# design.net
KiCad netlist of a schematic drawn in Altium Designer
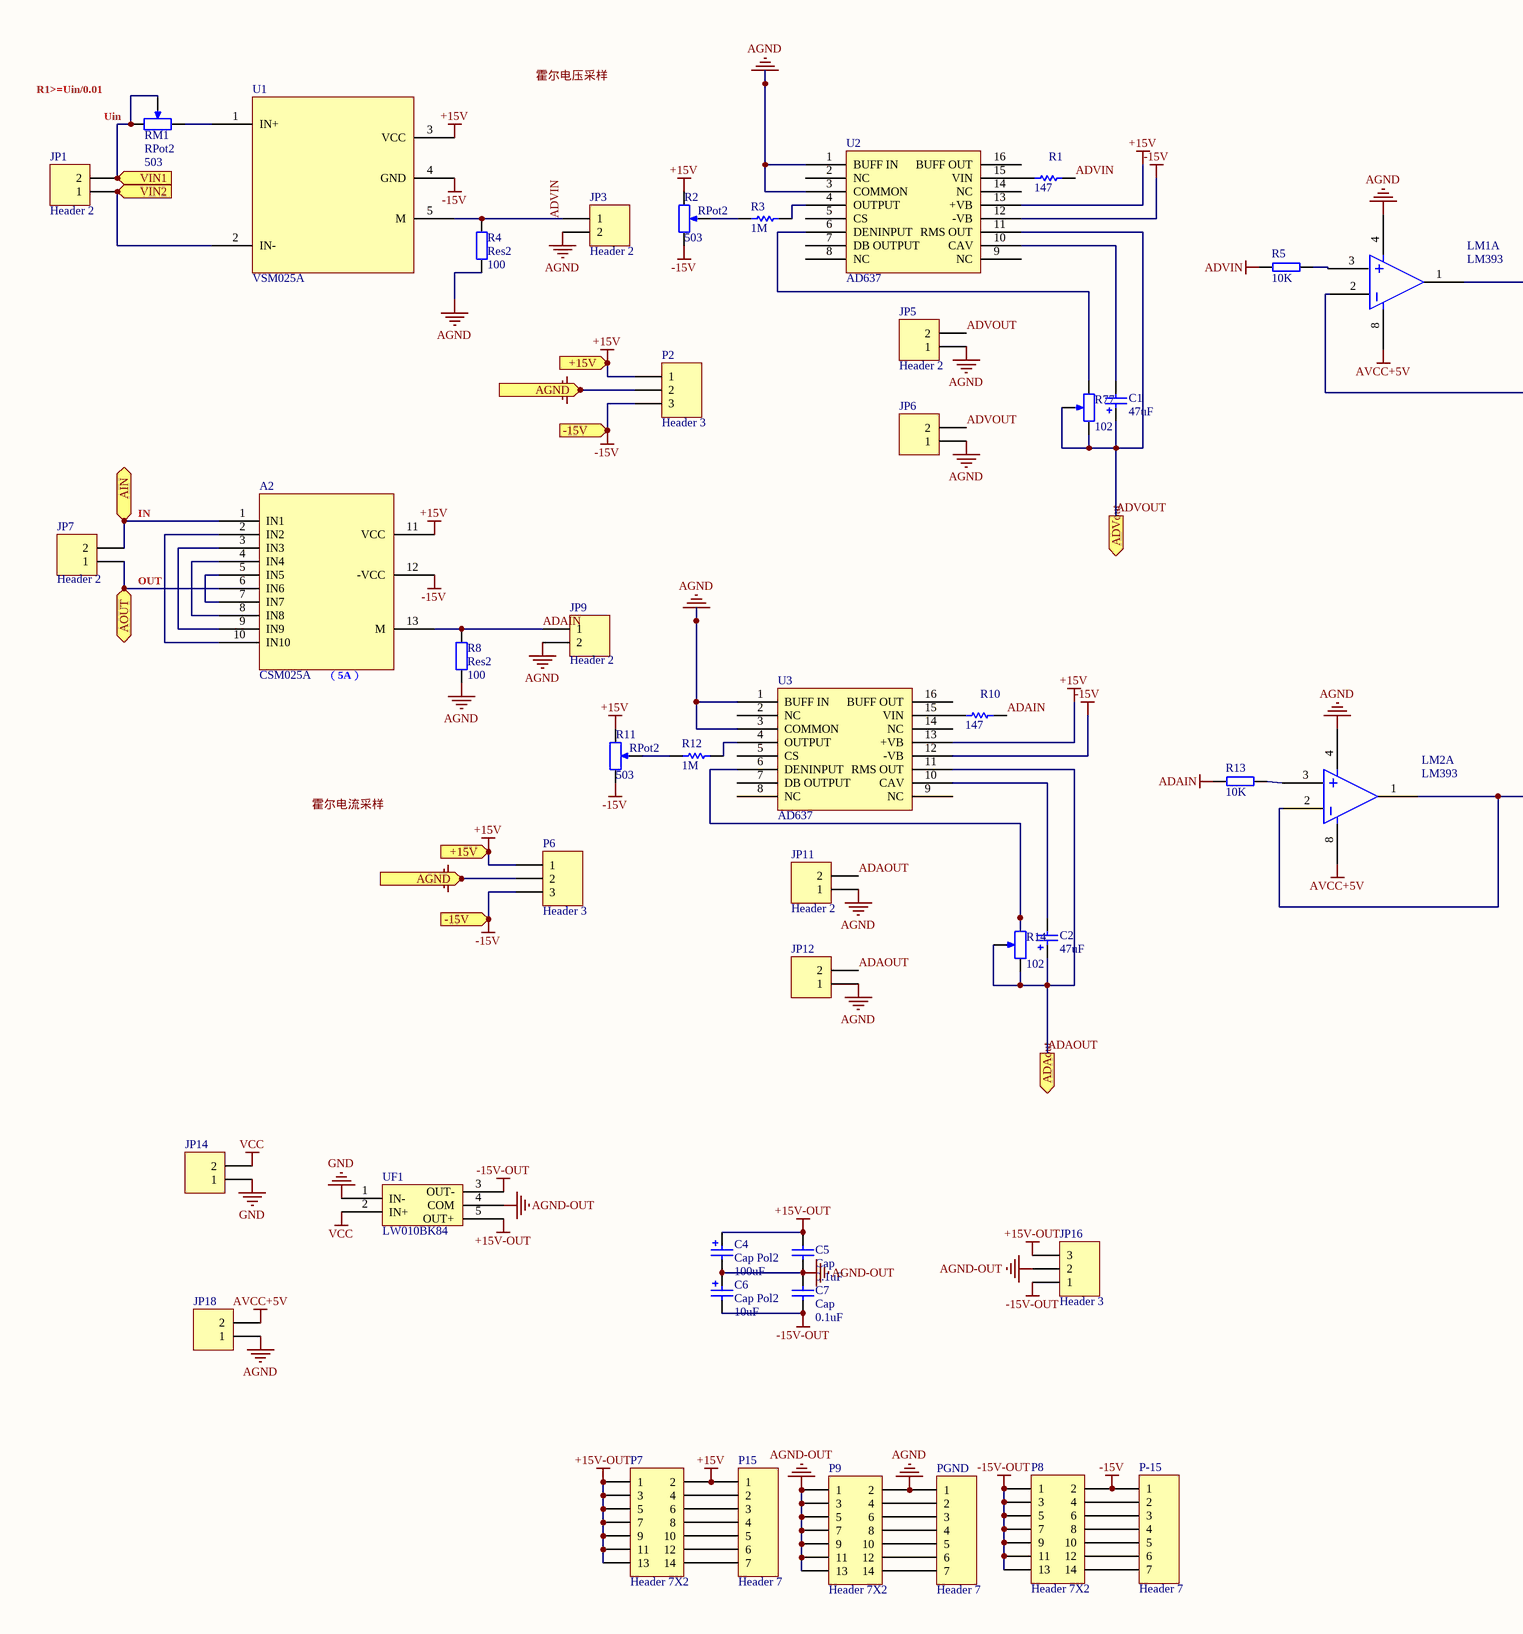
[diagram p0: 输出采样部分.SchDoc, left]
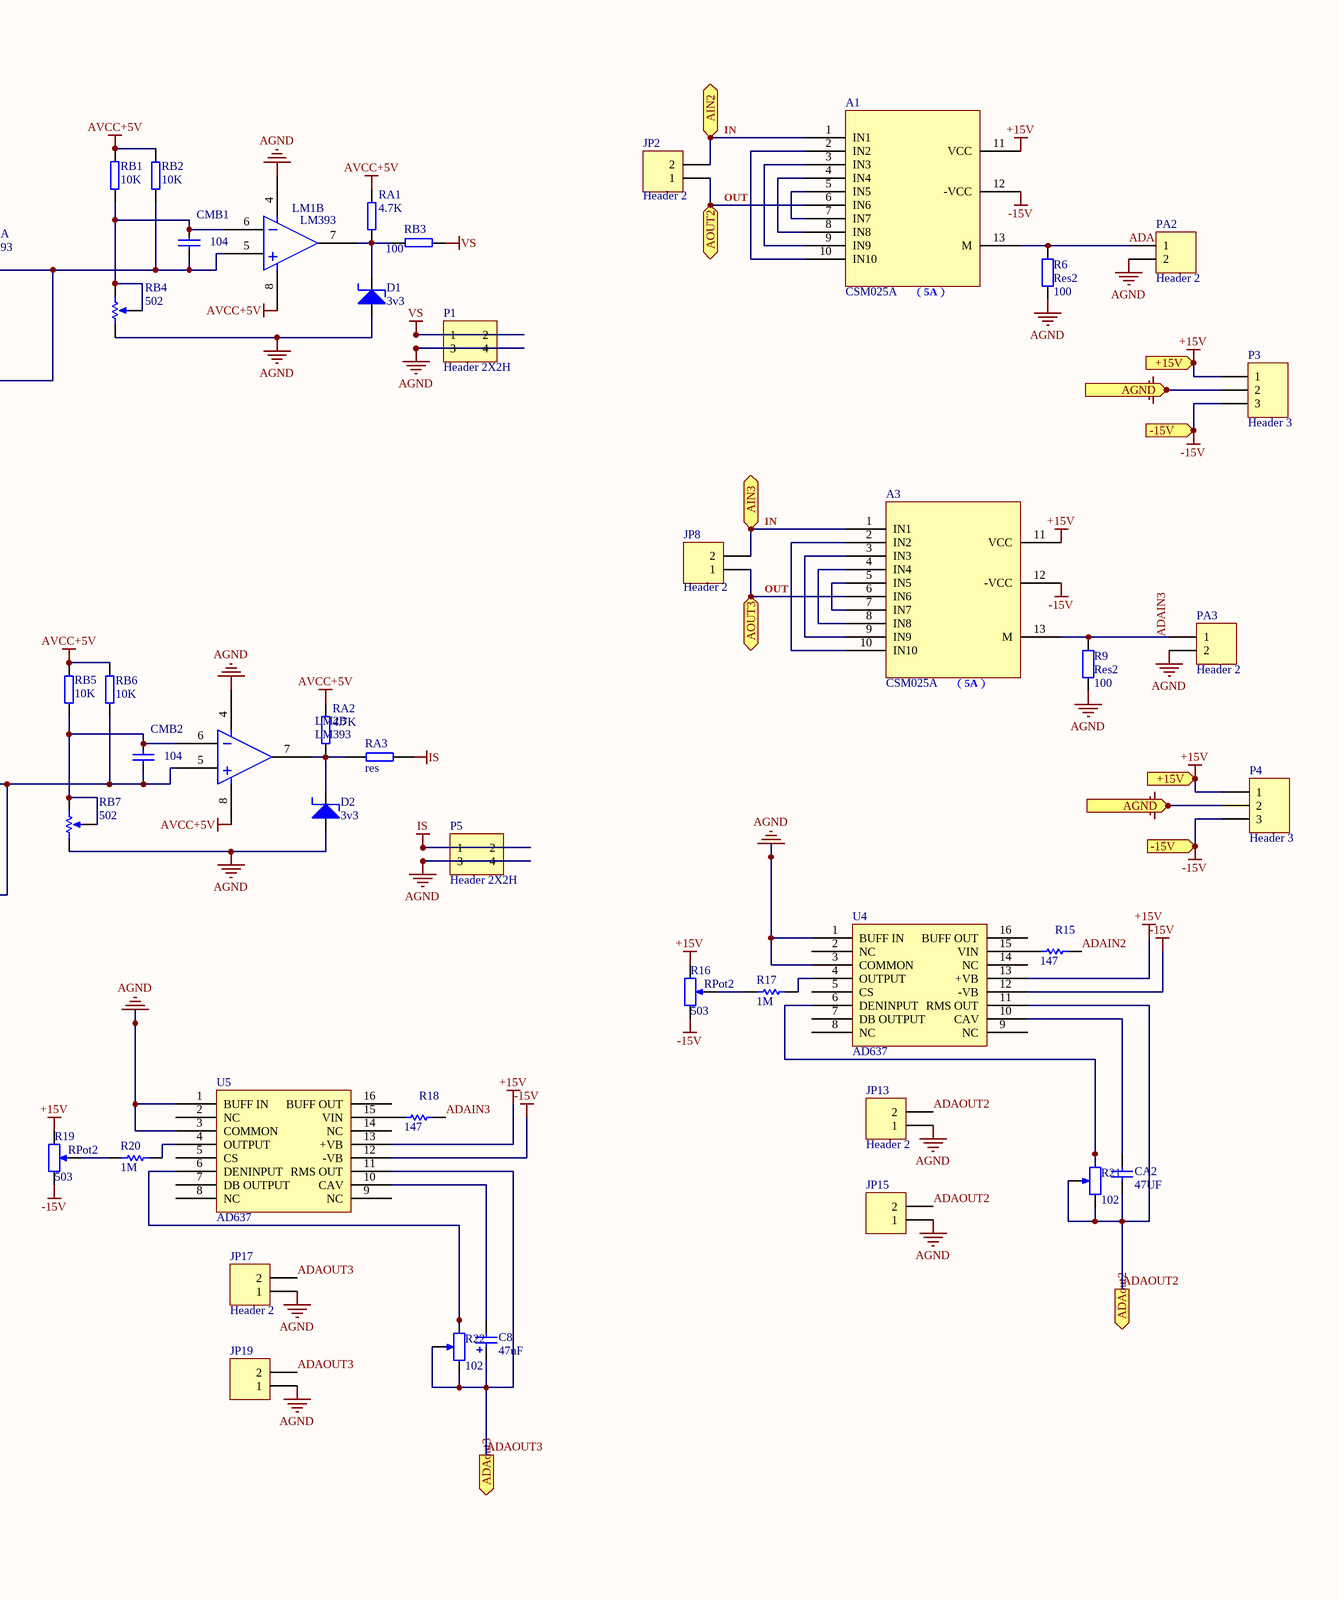
[diagram p1: 输出采样部分.SchDoc, right]

(export (version "E")
  (design (tool "Eeschema 10.0.6"))
  (components
    (comp (ref "A1") (value "CSM025A") (footprint "csm025a") (libsource (lib "*") (part "CSM025A")))
    (comp (ref "A2") (value "CSM025A") (footprint "csm025a") (libsource (lib "*") (part "CSM025A")))
    (comp (ref "A3") (value "CSM025A") (footprint "csm025a") (libsource (lib "*") (part "CSM025A")))
    (comp (ref "C1")
      (value "47uF")
      (footprint "CAPR5-4X5")
      (description "Polarized Capacitor (Radial)")
      (fields (field (name "PUBLISHER") "Altium Limited"))
      (libsource (lib "Miscellaneous Devices") (part "Cap Pol1"))
    )
    (comp (ref "C2")
      (value "47uF")
      (footprint "CAPR5-4X5")
      (description "Polarized Capacitor (Radial)")
      (fields (field (name "PUBLISHER") "Altium Limited"))
      (libsource (lib "Miscellaneous Devices") (part "Cap Pol1"))
    )
    (comp (ref "C4")
      (value "Cap Pol2")
      (footprint "CAPR2.54-5.1x3.2")
      (description "Polarized Capacitor (Axial)")
      (fields
        (field (name "MANUFACTURER") "Generic Components")
        (field (name "ALTIUM_VALUE") "100uF")
        (field (name "PUBLISHER") "Altium Hobart Technology Centre")
      )
      (libsource (lib "Miscellaneous Devices") (part "Cap Pol2"))
    )
    (comp (ref "C5")
      (value "Cap")
      (footprint "CAPR2.54-5.1x3.2")
      (description "Capacitor")
      (fields
        (field (name "MANUFACTURER") "Generic Components")
        (field (name "ALTIUM_VALUE") "0.1uF")
        (field (name "PUBLISHER") "Altium Hobart Technology Centre")
      )
      (libsource (lib "Miscellaneous Devices") (part "Cap"))
    )
    (comp (ref "C6")
      (value "Cap Pol2")
      (footprint "CAPR2.54-5.1x3.2")
      (description "Polarized Capacitor (Axial)")
      (fields
        (field (name "MANUFACTURER") "Generic Components")
        (field (name "ALTIUM_VALUE") "10uF")
        (field (name "PUBLISHER") "Altium Hobart Technology Centre")
      )
      (libsource (lib "Miscellaneous Devices") (part "Cap Pol2"))
    )
    (comp (ref "C7")
      (value "Cap")
      (footprint "CAPR2.54-5.1x3.2")
      (description "Capacitor")
      (fields
        (field (name "MANUFACTURER") "Generic Components")
        (field (name "ALTIUM_VALUE") "0.1uF")
        (field (name "PUBLISHER") "Altium Hobart Technology Centre")
      )
      (libsource (lib "Miscellaneous Devices") (part "Cap"))
    )
    (comp (ref "C8")
      (value "47uF")
      (footprint "CAPR5-4X5")
      (description "Polarized Capacitor (Radial)")
      (fields (field (name "PUBLISHER") "Altium Limited"))
      (libsource (lib "Miscellaneous Devices") (part "Cap Pol1"))
    )
    (comp (ref "CA2") (value "47UF") (footprint "CAP") (libsource (lib "自建库") (part "CAP")))
    (comp (ref "CMB1")
      (value "104")
      (footprint "CAP")
      (description "瓷片/无极电容")
      (fields (field (name "Comment") "C"))
      (libsource (lib "Mine") (part "CC"))
    )
    (comp (ref "CMB2")
      (value "104")
      (footprint "CAP")
      (description "瓷片/无极电容")
      (fields (field (name "Comment") "C"))
      (libsource (lib "Mine") (part "CC"))
    )
    (comp (ref "D1") (value "3v3") (footprint "DIO7.1-3.9x1.9") (libsource (lib "自建库") (part "稳压二极管")))
    (comp (ref "D2") (value "3v3") (footprint "DIO7.1-3.9x1.9") (libsource (lib "自建库") (part "稳压二极管")))
    (comp (ref "JP1")
      (value "Header 2")
      (footprint "tie-in")
      (description "Header, 2-Pin")
      (fields (field (name "MANUFACTURER") "Generic Components"))
      (libsource (lib "Miscellaneous Connectors") (part "Header 2"))
    )
    (comp (ref "JP2")
      (value "Header 2")
      (footprint "tie-in")
      (description "Header, 2-Pin")
      (fields (field (name "MANUFACTURER") "Generic Components"))
      (libsource (lib "Miscellaneous Connectors") (part "Header 2"))
    )
    (comp (ref "JP3")
      (value "Header 2")
      (footprint "HDR1X2")
      (description "Header, 2-Pin")
      (fields (field (name "MANUFACTURER") "Generic Components"))
      (libsource (lib "") (part "Header 2_1"))
    )
    (comp (ref "JP5")
      (value "Header 2")
      (footprint "HDR1X2")
      (description "Header, 2-Pin")
      (fields (field (name "MANUFACTURER") "Generic Components"))
      (libsource (lib "Miscellaneous Connectors") (part "Header 2"))
    )
    (comp (ref "JP6")
      (value "~")
      (footprint "HDR1X2")
      (description "Header, 2-Pin")
      (fields (field (name "MANUFACTURER") "Generic Components"))
      (libsource (lib "Miscellaneous Connectors") (part "Header 2"))
    )
    (comp (ref "JP7")
      (value "Header 2")
      (footprint "tie-in")
      (description "Header, 2-Pin")
      (fields (field (name "MANUFACTURER") "Generic Components"))
      (libsource (lib "Miscellaneous Connectors") (part "Header 2"))
    )
    (comp (ref "JP8")
      (value "Header 2")
      (footprint "tie-in")
      (description "Header, 2-Pin")
      (fields (field (name "MANUFACTURER") "Generic Components"))
      (libsource (lib "Miscellaneous Connectors") (part "Header 2"))
    )
    (comp (ref "JP9")
      (value "Header 2")
      (footprint "HDR1X2")
      (description "Header, 2-Pin")
      (fields (field (name "MANUFACTURER") "Generic Components"))
      (libsource (lib "") (part "Header 2_1"))
    )
    (comp (ref "JP11")
      (value "Header 2")
      (footprint "HDR1X2")
      (description "Header, 2-Pin")
      (fields (field (name "MANUFACTURER") "Generic Components"))
      (libsource (lib "Miscellaneous Connectors") (part "Header 2"))
    )
    (comp (ref "JP12")
      (value "~")
      (footprint "HDR1X2")
      (description "Header, 2-Pin")
      (fields (field (name "MANUFACTURER") "Generic Components"))
      (libsource (lib "Miscellaneous Connectors") (part "Header 2"))
    )
    (comp (ref "JP13")
      (value "Header 2")
      (footprint "HDR1X2")
      (description "Header, 2-Pin")
      (fields (field (name "MANUFACTURER") "Generic Components"))
      (libsource (lib "Miscellaneous Connectors") (part "Header 2"))
    )
    (comp (ref "JP14")
      (value "~")
      (footprint "tie-in")
      (description "Header, 2-Pin")
      (fields (field (name "MANUFACTURER") "Generic Components"))
      (libsource (lib "Miscellaneous Connectors") (part "Header 2"))
    )
    (comp (ref "JP15")
      (value "~")
      (footprint "HDR1X2")
      (description "Header, 2-Pin")
      (fields (field (name "MANUFACTURER") "Generic Components"))
      (libsource (lib "Miscellaneous Connectors") (part "Header 2"))
    )
    (comp (ref "JP16")
      (value "Header 3")
      (footprint "HDR1X3")
      (description "Header, 3-Pin")
      (fields (field (name "MANUFACTURER") "Generic Components"))
      (libsource (lib "") (part "Header 3_1"))
    )
    (comp (ref "JP17")
      (value "Header 2")
      (footprint "HDR1X2")
      (description "Header, 2-Pin")
      (fields (field (name "MANUFACTURER") "Generic Components"))
      (libsource (lib "Miscellaneous Connectors") (part "Header 2"))
    )
    (comp (ref "JP18")
      (value "~")
      (footprint "tie-in")
      (description "Header, 2-Pin")
      (fields (field (name "MANUFACTURER") "Generic Components"))
      (libsource (lib "Miscellaneous Connectors") (part "Header 2"))
    )
    (comp (ref "JP19")
      (value "~")
      (footprint "HDR1X2")
      (description "Header, 2-Pin")
      (fields (field (name "MANUFACTURER") "Generic Components"))
      (libsource (lib "Miscellaneous Connectors") (part "Header 2"))
    )
    (comp (ref "LM1") (value "LM393") (footprint "DIP8") (libsource (lib "电子钟r") (part "LM393")))
    (comp (ref "LM2") (value "LM393") (footprint "DIP8") (libsource (lib "自建库") (part "LM393")))
    (comp (ref "P-15")
      (value "Header 7")
      (footprint "HDR1X7")
      (description "Header, 7-Pin")
      (fields (field (name "PUBLISHER") "Altium Limited"))
      (libsource (lib "Miscellaneous Connectors") (part "Header 7"))
    )
    (comp (ref "P1")
      (value "Header 2X2H")
      (footprint "HDR2X2H")
      (description "Header, 2-Pin, Dual row, Right Angle")
      (fields (field (name "PUBLISHER") "Altium Limited"))
      (libsource (lib "Miscellaneous Connectors") (part "Header 2X2H"))
    )
    (comp (ref "P2")
      (value "Header 3")
      (footprint "HDR1X3")
      (description "Header, 3-Pin")
      (fields (field (name "PUBLISHER") "Altium Limited"))
      (libsource (lib "Miscellaneous Connectors") (part "Header 3"))
    )
    (comp (ref "P3")
      (value "Header 3")
      (footprint "HDR1X3")
      (description "Header, 3-Pin")
      (fields (field (name "PUBLISHER") "Altium Limited"))
      (libsource (lib "Miscellaneous Connectors") (part "Header 3"))
    )
    (comp (ref "P4")
      (value "Header 3")
      (footprint "HDR1X3")
      (description "Header, 3-Pin")
      (fields (field (name "PUBLISHER") "Altium Limited"))
      (libsource (lib "Miscellaneous Connectors") (part "Header 3"))
    )
    (comp (ref "P5")
      (value "Header 2X2H")
      (footprint "HDR2X2H")
      (description "Header, 2-Pin, Dual row, Right Angle")
      (fields (field (name "PUBLISHER") "Altium Limited"))
      (libsource (lib "Miscellaneous Connectors") (part "Header 2X2H"))
    )
    (comp (ref "P6")
      (value "Header 3")
      (footprint "HDR1X3")
      (description "Header, 3-Pin")
      (fields (field (name "PUBLISHER") "Altium Limited"))
      (libsource (lib "Miscellaneous Connectors") (part "Header 3"))
    )
    (comp (ref "P7")
      (value "Header 7X2")
      (footprint "HDR2X7")
      (description "Header, 7-Pin, Dual row")
      (fields (field (name "PUBLISHER") "Altium Limited"))
      (libsource (lib "Miscellaneous Connectors") (part "Header 7X2"))
    )
    (comp (ref "P8")
      (value "Header 7X2")
      (footprint "HDR2X7")
      (description "Header, 7-Pin, Dual row")
      (fields (field (name "PUBLISHER") "Altium Limited"))
      (libsource (lib "Miscellaneous Connectors") (part "Header 7X2"))
    )
    (comp (ref "P9")
      (value "Header 7X2")
      (footprint "HDR2X7")
      (description "Header, 7-Pin, Dual row")
      (fields (field (name "PUBLISHER") "Altium Limited"))
      (libsource (lib "Miscellaneous Connectors") (part "Header 7X2"))
    )
    (comp (ref "P15")
      (value "Header 7")
      (footprint "HDR1X7")
      (description "Header, 7-Pin")
      (fields (field (name "PUBLISHER") "Altium Limited"))
      (libsource (lib "Miscellaneous Connectors") (part "Header 7"))
    )
    (comp (ref "PA2")
      (value "Header 2")
      (footprint "HDR1X2")
      (description "Header, 2-Pin")
      (fields (field (name "PUBLISHER") "Altium Limited"))
      (libsource (lib "") (part "Header 2_1"))
    )
    (comp (ref "PA3")
      (value "Header 2")
      (footprint "HDR1X2")
      (description "Header, 2-Pin")
      (fields (field (name "PUBLISHER") "Altium Limited"))
      (libsource (lib "") (part "Header 2_1"))
    )
    (comp (ref "PGND")
      (value "Header 7")
      (footprint "HDR1X7")
      (description "Header, 7-Pin")
      (fields (field (name "PUBLISHER") "Altium Limited"))
      (libsource (lib "Miscellaneous Connectors") (part "Header 7"))
    )
    (comp (ref "R1")
      (value "147")
      (footprint "RES")
      (description "Resistor")
      (fields (field (name "PUBLISHER") "Altium Limited"))
      (libsource (lib "Miscellaneous Devices") (part "Res1"))
    )
    (comp (ref "R2")
      (value "RPot2")
      (footprint "滑阻")
      (description "Potentiometer")
      (fields
        (field (name "MANUFACTURER") "Generic Components")
        (field (name "ALTIUM_VALUE") "503")
        (field (name "PUBLISHER") "Altium Hobart Technology Centre")
      )
      (libsource (lib "") (part "RPot2_2"))
    )
    (comp (ref "R3")
      (value "1M")
      (footprint "RES")
      (description "Resistor")
      (fields (field (name "PUBLISHER") "Altium Limited"))
      (libsource (lib "Miscellaneous Devices") (part "Res1"))
    )
    (comp (ref "R4")
      (value "Res2")
      (footprint "RES")
      (description "Resistor")
      (fields
        (field (name "MANUFACTURER") "Generic Components")
        (field (name "ALTIUM_VALUE") "100")
        (field (name "PUBLISHER") "Altium Hobart Technology Centre")
      )
      (libsource (lib "Miscellaneous Devices") (part "Res2"))
    )
    (comp (ref "R5") (value "10K") (footprint "RES") (description "R") (libsource (lib "Mine") (part "R")))
    (comp (ref "R6")
      (value "Res2")
      (footprint "RES")
      (description "Resistor")
      (fields
        (field (name "MANUFACTURER") "Generic Components")
        (field (name "ALTIUM_VALUE") "100")
        (field (name "PUBLISHER") "Altium Hobart Technology Centre")
      )
      (libsource (lib "Miscellaneous Devices") (part "Res2"))
    )
    (comp (ref "R8")
      (value "Res2")
      (footprint "RES")
      (description "Resistor")
      (fields
        (field (name "MANUFACTURER") "Generic Components")
        (field (name "ALTIUM_VALUE") "100")
        (field (name "PUBLISHER") "Altium Hobart Technology Centre")
      )
      (libsource (lib "Miscellaneous Devices") (part "Res2"))
    )
    (comp (ref "R9")
      (value "Res2")
      (footprint "RES")
      (description "Resistor")
      (fields
        (field (name "MANUFACTURER") "Generic Components")
        (field (name "ALTIUM_VALUE") "100")
        (field (name "PUBLISHER") "Altium Hobart Technology Centre")
      )
      (libsource (lib "Miscellaneous Devices") (part "Res2"))
    )
    (comp (ref "R10")
      (value "147")
      (footprint "RES")
      (description "Resistor")
      (fields (field (name "PUBLISHER") "Altium Limited"))
      (libsource (lib "Miscellaneous Devices") (part "Res1"))
    )
    (comp (ref "R11")
      (value "RPot2")
      (footprint "滑阻")
      (description "Potentiometer")
      (fields
        (field (name "MANUFACTURER") "Generic Components")
        (field (name "ALTIUM_VALUE") "503")
        (field (name "PUBLISHER") "Altium Hobart Technology Centre")
      )
      (libsource (lib "") (part "RPot2_2"))
    )
    (comp (ref "R12")
      (value "1M")
      (footprint "RES")
      (description "Resistor")
      (fields (field (name "PUBLISHER") "Altium Limited"))
      (libsource (lib "Miscellaneous Devices") (part "Res1"))
    )
    (comp (ref "R13") (value "10K") (footprint "RES") (description "R") (libsource (lib "Mine") (part "R")))
    (comp (ref "R14")
      (value "102")
      (footprint "滑阻")
      (description "Potentiometer")
      (fields
        (field (name "MANUFACTURER") "Generic Components")
        (field (name "PUBLISHER") "Altium Hobart Technology Centre")
      )
      (libsource (lib "Miscellaneous Devices") (part "RPot2"))
    )
    (comp (ref "R15")
      (value "147")
      (footprint "RES")
      (description "Resistor")
      (fields (field (name "PUBLISHER") "Altium Limited"))
      (libsource (lib "Miscellaneous Devices") (part "Res1"))
    )
    (comp (ref "R16")
      (value "RPot2")
      (footprint "滑阻")
      (description "Potentiometer")
      (fields
        (field (name "MANUFACTURER") "Generic Components")
        (field (name "ALTIUM_VALUE") "503")
        (field (name "PUBLISHER") "Altium Hobart Technology Centre")
      )
      (libsource (lib "") (part "RPot2_2"))
    )
    (comp (ref "R17")
      (value "1M")
      (footprint "RES")
      (description "Resistor")
      (fields (field (name "PUBLISHER") "Altium Limited"))
      (libsource (lib "Miscellaneous Devices") (part "Res1"))
    )
    (comp (ref "R18")
      (value "147")
      (footprint "RES")
      (description "Resistor")
      (fields (field (name "PUBLISHER") "Altium Limited"))
      (libsource (lib "Miscellaneous Devices") (part "Res1"))
    )
    (comp (ref "R19")
      (value "RPot2")
      (footprint "滑阻")
      (description "Potentiometer")
      (fields
        (field (name "MANUFACTURER") "Generic Components")
        (field (name "ALTIUM_VALUE") "503")
        (field (name "PUBLISHER") "Altium Hobart Technology Centre")
      )
      (libsource (lib "") (part "RPot2_2"))
    )
    (comp (ref "R20")
      (value "1M")
      (footprint "RES")
      (description "Resistor")
      (fields (field (name "PUBLISHER") "Altium Limited"))
      (libsource (lib "Miscellaneous Devices") (part "Res1"))
    )
    (comp (ref "R21")
      (value "102")
      (footprint "滑阻")
      (description "Potentiometer")
      (fields
        (field (name "MANUFACTURER") "Generic Components")
        (field (name "PUBLISHER") "Altium Hobart Technology Centre")
      )
      (libsource (lib "Miscellaneous Devices") (part "RPot2"))
    )
    (comp (ref "R22")
      (value "102")
      (footprint "滑阻")
      (description "Potentiometer")
      (fields
        (field (name "MANUFACTURER") "Generic Components")
        (field (name "PUBLISHER") "Altium Hobart Technology Centre")
      )
      (libsource (lib "Miscellaneous Devices") (part "RPot2"))
    )
    (comp (ref "R77")
      (value "102")
      (footprint "滑阻")
      (description "Potentiometer")
      (fields
        (field (name "MANUFACTURER") "Generic Components")
        (field (name "PUBLISHER") "Altium Hobart Technology Centre")
      )
      (libsource (lib "") (part "RPot2_3"))
    )
    (comp (ref "RA1") (value "4.7K") (footprint "RES") (description "R") (libsource (lib "Mine") (part "R")))
    (comp (ref "RA2") (value "4.7K") (footprint "RES") (description "R") (libsource (lib "Mine") (part "R")))
    (comp (ref "RA3") (value "res") (footprint "RES") (libsource (lib "自建库") (part "res")))
    (comp (ref "RB1") (value "10K") (footprint "RES") (description "R") (libsource (lib "Mine") (part "R")))
    (comp (ref "RB2") (value "10K") (footprint "RES") (description "R") (libsource (lib "Mine") (part "R")))
    (comp (ref "RB3") (value "100") (footprint "RES") (description "R") (libsource (lib "Mine") (part "R")))
    (comp (ref "RB4")
      (value "502")
      (footprint "VR5")
      (description "Potentiometer")
      (fields (field (name "Comment") "504") (field (name "PUBLISHER") "Altium Limited"))
      (libsource (lib "Miscellaneous Devices") (part "RPot"))
    )
    (comp (ref "RB5") (value "10K") (footprint "RES") (description "R") (libsource (lib "Mine") (part "R")))
    (comp (ref "RB6") (value "10K") (footprint "RES") (description "R") (libsource (lib "Mine") (part "R")))
    (comp (ref "RB7")
      (value "502")
      (footprint "VR5")
      (description "Potentiometer")
      (fields (field (name "Comment") "504") (field (name "PUBLISHER") "Altium Limited"))
      (libsource (lib "Miscellaneous Devices") (part "RPot"))
    )
    (comp (ref "RM1")
      (value "RPot2")
      (footprint "滑阻")
      (description "Potentiometer")
      (fields
        (field (name "MANUFACTURER") "Generic Components")
        (field (name "ALTIUM_VALUE") "503")
        (field (name "PUBLISHER") "Altium Hobart Technology Centre")
      )
      (libsource (lib "") (part "RPot2_1"))
    )
    (comp (ref "U1") (value "VSM025A") (footprint "vsm025a") (libsource (lib "*") (part "VSM025A")))
    (comp (ref "U2") (value "AD637") (footprint "AD637转接板") (libsource (lib "自建库") (part "AD637")))
    (comp (ref "U3") (value "AD637") (footprint "AD637转接板") (libsource (lib "自建库") (part "AD637")))
    (comp (ref "U4") (value "AD637") (footprint "AD637转接板") (libsource (lib "自建库") (part "AD637")))
    (comp (ref "U5") (value "AD637") (footprint "AD637转接板") (libsource (lib "自建库") (part "AD637")))
    (comp (ref "UF1") (value "LW010BK84") (footprint "LW010BK84") (libsource (lib "自建库") (part "LW010BK84")))
  )
  (nets
    (net (code "1") (name "+15V") (class "Default")
      (node (ref "A1") (pin "11") (pinfunction "VCC_11") (pintype "passive"))
      (node (ref "A2") (pin "11") (pinfunction "VCC_11") (pintype "passive"))
      (node (ref "A3") (pin "11") (pinfunction "VCC_11") (pintype "passive"))
      (node (ref "P15") (pin "1") (pinfunction "1_1") (pintype "passive"))
      (node (ref "P2") (pin "1") (pinfunction "1_1") (pintype "passive"))
      (node (ref "P3") (pin "1") (pinfunction "1_1") (pintype "passive"))
      (node (ref "P4") (pin "1") (pinfunction "1_1") (pintype "passive"))
      (node (ref "P6") (pin "1") (pinfunction "1_1") (pintype "passive"))
      (node (ref "P7") (pin "2") (pinfunction "2_2") (pintype "passive"))
      (node (ref "R11") (pin "2") (pinfunction "BOT_2") (pintype "passive"))
      (node (ref "R16") (pin "2") (pinfunction "BOT_2") (pintype "passive"))
      (node (ref "R19") (pin "2") (pinfunction "BOT_2") (pintype "passive"))
      (node (ref "R2") (pin "2") (pinfunction "BOT_2") (pintype "passive"))
      (node (ref "U1") (pin "3") (pinfunction "VCC_3") (pintype "passive"))
      (node (ref "U2") (pin "13") (pinfunction "+VB_13") (pintype "passive"))
      (node (ref "U3") (pin "13") (pinfunction "+VB_13") (pintype "passive"))
      (node (ref "U4") (pin "13") (pinfunction "+VB_13") (pintype "passive"))
      (node (ref "U5") (pin "13") (pinfunction "+VB_13") (pintype "passive"))
    )
    (net (code "2") (name "+15V-OUT") (class "Default")
      (node (ref "C4") (pin "1") (pinfunction "1_1") (pintype "passive"))
      (node (ref "C5") (pin "2") (pinfunction "2_2") (pintype "passive"))
      (node (ref "JP16") (pin "3") (pinfunction "3_3") (pintype "passive"))
      (node (ref "P7") (pin "1") (pinfunction "1_1") (pintype "passive"))
      (node (ref "P7") (pin "11") (pinfunction "11_11") (pintype "passive"))
      (node (ref "P7") (pin "13") (pinfunction "13_13") (pintype "passive"))
      (node (ref "P7") (pin "3") (pinfunction "3_3") (pintype "passive"))
      (node (ref "P7") (pin "5") (pinfunction "5_5") (pintype "passive"))
      (node (ref "P7") (pin "7") (pinfunction "7_7") (pintype "passive"))
      (node (ref "P7") (pin "9") (pinfunction "9_9") (pintype "passive"))
      (node (ref "UF1") (pin "5") (pinfunction "OUT+_5") (pintype "passive"))
    )
    (net (code "3") (name "-15V") (class "Default")
      (node (ref "A1") (pin "12") (pinfunction "-VCC_12") (pintype "passive"))
      (node (ref "A2") (pin "12") (pinfunction "-VCC_12") (pintype "passive"))
      (node (ref "A3") (pin "12") (pinfunction "-VCC_12") (pintype "passive"))
      (node (ref "P-15") (pin "1") (pinfunction "1_1") (pintype "passive"))
      (node (ref "P2") (pin "3") (pinfunction "3_3") (pintype "passive"))
      (node (ref "P3") (pin "3") (pinfunction "3_3") (pintype "passive"))
      (node (ref "P4") (pin "3") (pinfunction "3_3") (pintype "passive"))
      (node (ref "P6") (pin "3") (pinfunction "3_3") (pintype "passive"))
      (node (ref "P8") (pin "2") (pinfunction "2_2") (pintype "passive"))
      (node (ref "R11") (pin "1") (pinfunction "TOP_1") (pintype "passive"))
      (node (ref "R16") (pin "1") (pinfunction "TOP_1") (pintype "passive"))
      (node (ref "R19") (pin "1") (pinfunction "TOP_1") (pintype "passive"))
      (node (ref "R2") (pin "1") (pinfunction "TOP_1") (pintype "passive"))
      (node (ref "U1") (pin "4") (pinfunction "GND_4") (pintype "passive"))
      (node (ref "U2") (pin "12") (pinfunction "-VB_12") (pintype "passive"))
      (node (ref "U3") (pin "12") (pinfunction "-VB_12") (pintype "passive"))
      (node (ref "U4") (pin "12") (pinfunction "-VB_12") (pintype "passive"))
      (node (ref "U5") (pin "12") (pinfunction "-VB_12") (pintype "passive"))
    )
    (net (code "4") (name "-15V-OUT") (class "Default")
      (node (ref "C6") (pin "2") (pinfunction "2_2") (pintype "passive"))
      (node (ref "C7") (pin "1") (pinfunction "1_1") (pintype "passive"))
      (node (ref "JP16") (pin "1") (pinfunction "1_1") (pintype "passive"))
      (node (ref "P8") (pin "1") (pinfunction "1_1") (pintype "passive"))
      (node (ref "P8") (pin "11") (pinfunction "11_11") (pintype "passive"))
      (node (ref "P8") (pin "13") (pinfunction "13_13") (pintype "passive"))
      (node (ref "P8") (pin "3") (pinfunction "3_3") (pintype "passive"))
      (node (ref "P8") (pin "5") (pinfunction "5_5") (pintype "passive"))
      (node (ref "P8") (pin "7") (pinfunction "7_7") (pintype "passive"))
      (node (ref "P8") (pin "9") (pinfunction "9_9") (pintype "passive"))
      (node (ref "UF1") (pin "3") (pinfunction "OUT-_3") (pintype "passive"))
    )
    (net (code "5") (name "/ADAIN2") (class "Default")
      (node (ref "A1") (pin "13") (pinfunction "M_13") (pintype "passive"))
      (node (ref "PA2") (pin "1") (pinfunction "1_1") (pintype "passive"))
      (node (ref "R15") (pin "2") (pinfunction "2_2") (pintype "passive"))
      (node (ref "R6") (pin "2") (pinfunction "2_2") (pintype "passive"))
    )
    (net (code "6") (name "/ADAIN3") (class "Default")
      (node (ref "A3") (pin "13") (pinfunction "M_13") (pintype "passive"))
      (node (ref "PA3") (pin "1") (pinfunction "1_1") (pintype "passive"))
      (node (ref "R18") (pin "2") (pinfunction "2_2") (pintype "passive"))
      (node (ref "R9") (pin "2") (pinfunction "2_2") (pintype "passive"))
    )
    (net (code "7") (name "/ADAOUT") (class "Default")
      (node (ref "C2") (pin "1") (pinfunction "1_1") (pintype "passive"))
      (node (ref "JP11") (pin "2") (pinfunction "2_2") (pintype "passive"))
      (node (ref "JP12") (pin "2") (pinfunction "2_2") (pintype "passive"))
      (node (ref "R14") (pin "2") (pinfunction "BOT_2") (pintype "passive"))
      (node (ref "R14") (pin "3") (pinfunction "TAP_3") (pintype "passive"))
      (node (ref "U3") (pin "11") (pinfunction "RMS_OUT_11") (pintype "passive"))
    )
    (net (code "8") (name "/ADAOUT2") (class "Default")
      (node (ref "CA2") (pin "1") (pinfunction "1_1") (pintype "passive"))
      (node (ref "JP13") (pin "2") (pinfunction "2_2") (pintype "passive"))
      (node (ref "JP15") (pin "2") (pinfunction "2_2") (pintype "passive"))
      (node (ref "R21") (pin "2") (pinfunction "BOT_2") (pintype "passive"))
      (node (ref "R21") (pin "3") (pinfunction "TAP_3") (pintype "passive"))
      (node (ref "U4") (pin "11") (pinfunction "RMS_OUT_11") (pintype "passive"))
    )
    (net (code "9") (name "/ADAOUT3") (class "Default")
      (node (ref "C8") (pin "1") (pinfunction "1_1") (pintype "passive"))
      (node (ref "JP17") (pin "2") (pinfunction "2_2") (pintype "passive"))
      (node (ref "JP19") (pin "2") (pinfunction "2_2") (pintype "passive"))
      (node (ref "R22") (pin "2") (pinfunction "BOT_2") (pintype "passive"))
      (node (ref "R22") (pin "3") (pinfunction "TAP_3") (pintype "passive"))
      (node (ref "U5") (pin "11") (pinfunction "RMS_OUT_11") (pintype "passive"))
    )
    (net (code "10") (name "/ADVOUT") (class "Default")
      (node (ref "C1") (pin "1") (pinfunction "1_1") (pintype "passive"))
      (node (ref "JP5") (pin "2") (pinfunction "2_2") (pintype "passive"))
      (node (ref "JP6") (pin "2") (pinfunction "2_2") (pintype "passive"))
      (node (ref "R77") (pin "1") (pinfunction "TOP_1") (pintype "passive"))
      (node (ref "R77") (pin "3") (pinfunction "TAP_3") (pintype "passive"))
      (node (ref "U2") (pin "11") (pinfunction "RMS_OUT_11") (pintype "passive"))
    )
    (net (code "11") (name "/AIN") (class "Default")
      (node (ref "A2") (pin "1") (pinfunction "IN1_1") (pintype "passive"))
      (node (ref "JP7") (pin "2") (pinfunction "2_2") (pintype "passive"))
    )
    (net (code "12") (name "/AIN2") (class "Default")
      (node (ref "A1") (pin "1") (pinfunction "IN1_1") (pintype "passive"))
      (node (ref "JP2") (pin "2") (pinfunction "2_2") (pintype "passive"))
    )
    (net (code "13") (name "/AIN3") (class "Default")
      (node (ref "A3") (pin "1") (pinfunction "IN1_1") (pintype "passive"))
      (node (ref "JP8") (pin "2") (pinfunction "2_2") (pintype "passive"))
    )
    (net (code "14") (name "/AOUT") (class "Default")
      (node (ref "A2") (pin "6") (pinfunction "IN6_6") (pintype "passive"))
      (node (ref "JP7") (pin "1") (pinfunction "1_1") (pintype "passive"))
    )
    (net (code "15") (name "/AOUT2") (class "Default")
      (node (ref "A1") (pin "6") (pinfunction "IN6_6") (pintype "passive"))
      (node (ref "JP2") (pin "1") (pinfunction "1_1") (pintype "passive"))
    )
    (net (code "16") (name "/AOUT3") (class "Default")
      (node (ref "A3") (pin "6") (pinfunction "IN6_6") (pintype "passive"))
      (node (ref "JP8") (pin "1") (pinfunction "1_1") (pintype "passive"))
    )
    (net (code "17") (name "/VIN1") (class "Default")
      (node (ref "JP1") (pin "2") (pinfunction "2_2") (pintype "passive"))
      (node (ref "RM1") (pin "2") (pinfunction "BOT_2") (pintype "passive"))
      (node (ref "RM1") (pin "3") (pinfunction "TAP_3") (pintype "passive"))
    )
    (net (code "18") (name "/VIN2") (class "Default")
      (node (ref "JP1") (pin "1") (pinfunction "1_1") (pintype "passive"))
      (node (ref "U1") (pin "2") (pinfunction "IN-_2") (pintype "passive"))
    )
    (net (code "21") (name "ADAIN") (class "Default")
      (node (ref "A2") (pin "13") (pinfunction "M_13") (pintype "passive"))
      (node (ref "JP9") (pin "1") (pinfunction "1_1") (pintype "passive"))
      (node (ref "R10") (pin "2") (pinfunction "2_2") (pintype "passive"))
      (node (ref "R13") (pin "2") (pinfunction "2_2") (pintype "passive"))
      (node (ref "R8") (pin "2") (pinfunction "2_2") (pintype "passive"))
    )
    (net (code "22") (name "ADVIN") (class "Default")
      (node (ref "JP3") (pin "1") (pinfunction "1_1") (pintype "passive"))
      (node (ref "R1") (pin "2") (pinfunction "2_2") (pintype "passive"))
      (node (ref "R4") (pin "2") (pinfunction "2_2") (pintype "passive"))
      (node (ref "R5") (pin "2") (pinfunction "2_2") (pintype "passive"))
      (node (ref "U1") (pin "5") (pinfunction "M_5") (pintype "passive"))
    )
    (net (code "23") (name "AGND") (class "Default")
      (node (ref "D1") (pin "1") (pinfunction "A_1") (pintype "passive"))
      (node (ref "D2") (pin "1") (pinfunction "A_1") (pintype "passive"))
      (node (ref "JP11") (pin "1") (pinfunction "1_1") (pintype "passive"))
      (node (ref "JP12") (pin "1") (pinfunction "1_1") (pintype "passive"))
      (node (ref "JP13") (pin "1") (pinfunction "1_1") (pintype "passive"))
      (node (ref "JP15") (pin "1") (pinfunction "1_1") (pintype "passive"))
      (node (ref "JP17") (pin "1") (pinfunction "1_1") (pintype "passive"))
      (node (ref "JP18") (pin "1") (pinfunction "1_1") (pintype "passive"))
      (node (ref "JP19") (pin "1") (pinfunction "1_1") (pintype "passive"))
      (node (ref "JP3") (pin "2") (pinfunction "2_2") (pintype "passive"))
      (node (ref "JP5") (pin "1") (pinfunction "1_1") (pintype "passive"))
      (node (ref "JP6") (pin "1") (pinfunction "1_1") (pintype "passive"))
      (node (ref "JP9") (pin "2") (pinfunction "2_2") (pintype "passive"))
      (node (ref "LM1") (pin "4") (pintype "passive"))
      (node (ref "LM2") (pin "4") (pintype "passive"))
      (node (ref "P1") (pin "3") (pinfunction "3_3") (pintype "passive"))
      (node (ref "P1") (pin "4") (pinfunction "4_4") (pintype "passive"))
      (node (ref "P2") (pin "2") (pinfunction "2_2") (pintype "passive"))
      (node (ref "P3") (pin "2") (pinfunction "2_2") (pintype "passive"))
      (node (ref "P4") (pin "2") (pinfunction "2_2") (pintype "passive"))
      (node (ref "P5") (pin "3") (pinfunction "3_3") (pintype "passive"))
      (node (ref "P5") (pin "4") (pinfunction "4_4") (pintype "passive"))
      (node (ref "P6") (pin "2") (pinfunction "2_2") (pintype "passive"))
      (node (ref "P9") (pin "2") (pinfunction "2_2") (pintype "passive"))
      (node (ref "PA2") (pin "2") (pinfunction "2_2") (pintype "passive"))
      (node (ref "PA3") (pin "2") (pinfunction "2_2") (pintype "passive"))
      (node (ref "PGND") (pin "1") (pinfunction "1_1") (pintype "passive"))
      (node (ref "R4") (pin "1") (pinfunction "1_1") (pintype "passive"))
      (node (ref "R6") (pin "1") (pinfunction "1_1") (pintype "passive"))
      (node (ref "R8") (pin "1") (pinfunction "1_1") (pintype "passive"))
      (node (ref "R9") (pin "1") (pinfunction "1_1") (pintype "passive"))
      (node (ref "RB4") (pin "1") (pinfunction "TOP_1") (pintype "passive"))
      (node (ref "RB7") (pin "1") (pinfunction "TOP_1") (pintype "passive"))
      (node (ref "U2") (pin "1") (pinfunction "BUFF_IN_1") (pintype "passive"))
      (node (ref "U2") (pin "3") (pinfunction "COMMON_3") (pintype "passive"))
      (node (ref "U3") (pin "1") (pinfunction "BUFF_IN_1") (pintype "passive"))
      (node (ref "U3") (pin "3") (pinfunction "COMMON_3") (pintype "passive"))
      (node (ref "U4") (pin "1") (pinfunction "BUFF_IN_1") (pintype "passive"))
      (node (ref "U4") (pin "3") (pinfunction "COMMON_3") (pintype "passive"))
      (node (ref "U5") (pin "1") (pinfunction "BUFF_IN_1") (pintype "passive"))
      (node (ref "U5") (pin "3") (pinfunction "COMMON_3") (pintype "passive"))
    )
    (net (code "24") (name "AGND-OUT") (class "Default")
      (node (ref "C4") (pin "2") (pinfunction "2_2") (pintype "passive"))
      (node (ref "C5") (pin "1") (pinfunction "1_1") (pintype "passive"))
      (node (ref "C6") (pin "1") (pinfunction "1_1") (pintype "passive"))
      (node (ref "C7") (pin "2") (pinfunction "2_2") (pintype "passive"))
      (node (ref "JP16") (pin "2") (pinfunction "2_2") (pintype "passive"))
      (node (ref "P9") (pin "1") (pinfunction "1_1") (pintype "passive"))
      (node (ref "P9") (pin "11") (pinfunction "11_11") (pintype "passive"))
      (node (ref "P9") (pin "13") (pinfunction "13_13") (pintype "passive"))
      (node (ref "P9") (pin "3") (pinfunction "3_3") (pintype "passive"))
      (node (ref "P9") (pin "5") (pinfunction "5_5") (pintype "passive"))
      (node (ref "P9") (pin "7") (pinfunction "7_7") (pintype "passive"))
      (node (ref "P9") (pin "9") (pinfunction "9_9") (pintype "passive"))
      (node (ref "UF1") (pin "4") (pinfunction "COM_4") (pintype "passive"))
    )
    (net (code "25") (name "AVCC+5V") (class "Default")
      (node (ref "JP18") (pin "2") (pinfunction "2_2") (pintype "passive"))
      (node (ref "LM1") (pin "8") (pintype "passive"))
      (node (ref "LM2") (pin "8") (pintype "passive"))
      (node (ref "RA1") (pin "2") (pinfunction "2_2") (pintype "passive"))
      (node (ref "RA2") (pin "2") (pinfunction "2_2") (pintype "passive"))
      (node (ref "RB1") (pin "1") (pinfunction "1_1") (pintype "passive"))
      (node (ref "RB2") (pin "2") (pinfunction "2_2") (pintype "passive"))
      (node (ref "RB5") (pin "1") (pinfunction "1_1") (pintype "passive"))
      (node (ref "RB6") (pin "2") (pinfunction "2_2") (pintype "passive"))
    )
    (net (code "26") (name "GND") (class "Default")
      (node (ref "JP14") (pin "1") (pinfunction "1_1") (pintype "passive"))
      (node (ref "UF1") (pin "1") (pinfunction "IN-_1") (pintype "passive"))
    )
    (net (code "27") (name "IS") (class "Default")
      (node (ref "P5") (pin "1") (pinfunction "1_1") (pintype "passive"))
      (node (ref "P5") (pin "2") (pinfunction "2_2") (pintype "passive"))
      (node (ref "RA3") (pin "2") (pinfunction "2_2") (pintype "passive"))
    )
    (net (code "28") (name "Net-(A1-IN3)") (class "Default")
      (node (ref "A1") (pin "3") (pinfunction "IN3_3") (pintype "passive"))
      (node (ref "A1") (pin "9") (pinfunction "IN9_9") (pintype "passive"))
    )
    (net (code "29") (name "Net-(A1-IN4)") (class "Default")
      (node (ref "A1") (pin "4") (pinfunction "IN4_4") (pintype "passive"))
      (node (ref "A1") (pin "8") (pinfunction "IN8_8") (pintype "passive"))
    )
    (net (code "30") (name "Net-(A1-IN5)") (class "Default")
      (node (ref "A1") (pin "5") (pinfunction "IN5_5") (pintype "passive"))
      (node (ref "A1") (pin "7") (pinfunction "IN7_7") (pintype "passive"))
    )
    (net (code "31") (name "Net-(A1-IN10)") (class "Default")
      (node (ref "A1") (pin "10") (pinfunction "IN10_10") (pintype "passive"))
      (node (ref "A1") (pin "2") (pinfunction "IN2_2") (pintype "passive"))
    )
    (net (code "32") (name "Net-(A2-IN3)") (class "Default")
      (node (ref "A2") (pin "3") (pinfunction "IN3_3") (pintype "passive"))
      (node (ref "A2") (pin "9") (pinfunction "IN9_9") (pintype "passive"))
    )
    (net (code "33") (name "Net-(A2-IN4)") (class "Default")
      (node (ref "A2") (pin "4") (pinfunction "IN4_4") (pintype "passive"))
      (node (ref "A2") (pin "8") (pinfunction "IN8_8") (pintype "passive"))
    )
    (net (code "34") (name "Net-(A2-IN5)") (class "Default")
      (node (ref "A2") (pin "5") (pinfunction "IN5_5") (pintype "passive"))
      (node (ref "A2") (pin "7") (pinfunction "IN7_7") (pintype "passive"))
    )
    (net (code "35") (name "Net-(A2-IN10)") (class "Default")
      (node (ref "A2") (pin "10") (pinfunction "IN10_10") (pintype "passive"))
      (node (ref "A2") (pin "2") (pinfunction "IN2_2") (pintype "passive"))
    )
    (net (code "36") (name "Net-(A3-IN3)") (class "Default")
      (node (ref "A3") (pin "3") (pinfunction "IN3_3") (pintype "passive"))
      (node (ref "A3") (pin "9") (pinfunction "IN9_9") (pintype "passive"))
    )
    (net (code "37") (name "Net-(A3-IN4)") (class "Default")
      (node (ref "A3") (pin "4") (pinfunction "IN4_4") (pintype "passive"))
      (node (ref "A3") (pin "8") (pinfunction "IN8_8") (pintype "passive"))
    )
    (net (code "38") (name "Net-(A3-IN5)") (class "Default")
      (node (ref "A3") (pin "5") (pinfunction "IN5_5") (pintype "passive"))
      (node (ref "A3") (pin "7") (pinfunction "IN7_7") (pintype "passive"))
    )
    (net (code "39") (name "Net-(A3-IN10)") (class "Default")
      (node (ref "A3") (pin "10") (pinfunction "IN10_10") (pintype "passive"))
      (node (ref "A3") (pin "2") (pinfunction "IN2_2") (pintype "passive"))
    )
    (net (code "40") (name "Net-(CMB1-Pad2)") (class "Default")
      (node (ref "CMB1") (pin "2") (pinfunction "2_2") (pintype "passive"))
      (node (ref "LM1") (pin "1") (pintype "passive"))
      (node (ref "LM1") (pin "2") (pintype "passive"))
      (node (ref "LM1") (pin "5") (pintype "passive"))
      (node (ref "RB2") (pin "1") (pinfunction "1_1") (pintype "passive"))
    )
    (net (code "41") (name "Net-(CMB2-Pad2)") (class "Default")
      (node (ref "CMB2") (pin "2") (pinfunction "2_2") (pintype "passive"))
      (node (ref "LM2") (pin "1") (pintype "passive"))
      (node (ref "LM2") (pin "2") (pintype "passive"))
      (node (ref "LM2") (pin "5") (pintype "passive"))
      (node (ref "RB6") (pin "1") (pinfunction "1_1") (pintype "passive"))
    )
    (net (code "42") (name "Net-(D1-K)") (class "Default")
      (node (ref "D1") (pin "2") (pinfunction "K_2") (pintype "passive"))
      (node (ref "LM1") (pin "7") (pintype "passive"))
      (node (ref "RA1") (pin "1") (pinfunction "1_1") (pintype "passive"))
      (node (ref "RB3") (pin "2") (pinfunction "2_2") (pintype "passive"))
    )
    (net (code "43") (name "Net-(D2-K)") (class "Default")
      (node (ref "D2") (pin "2") (pinfunction "K_2") (pintype "passive"))
      (node (ref "LM2") (pin "7") (pintype "passive"))
      (node (ref "RA2") (pin "1") (pinfunction "1_1") (pintype "passive"))
      (node (ref "RA3") (pin "1") (pinfunction "1_1") (pintype "passive"))
    )
    (net (code "44") (name "Net-(LM1-Pad3)") (class "Default")
      (node (ref "LM1") (pin "3") (pintype "passive"))
      (node (ref "R5") (pin "1") (pinfunction "1_1") (pintype "passive"))
    )
    (net (code "45") (name "Net-(LM2-Pad3)") (class "Default")
      (node (ref "LM2") (pin "3") (pintype "passive"))
      (node (ref "R13") (pin "1") (pinfunction "1_1") (pintype "passive"))
    )
    (net (code "46") (name "Net-(P-15-Pad2)") (class "Default")
      (node (ref "P-15") (pin "2") (pinfunction "2_2") (pintype "passive"))
      (node (ref "P8") (pin "4") (pinfunction "4_4") (pintype "passive"))
    )
    (net (code "47") (name "Net-(P-15-Pad3)") (class "Default")
      (node (ref "P-15") (pin "3") (pinfunction "3_3") (pintype "passive"))
      (node (ref "P8") (pin "6") (pinfunction "6_6") (pintype "passive"))
    )
    (net (code "48") (name "Net-(P-15-Pad4)") (class "Default")
      (node (ref "P-15") (pin "4") (pinfunction "4_4") (pintype "passive"))
      (node (ref "P8") (pin "8") (pinfunction "8_8") (pintype "passive"))
    )
    (net (code "49") (name "Net-(P-15-Pad5)") (class "Default")
      (node (ref "P-15") (pin "5") (pinfunction "5_5") (pintype "passive"))
      (node (ref "P8") (pin "10") (pinfunction "10_10") (pintype "passive"))
    )
    (net (code "50") (name "Net-(P-15-Pad6)") (class "Default")
      (node (ref "P-15") (pin "6") (pinfunction "6_6") (pintype "passive"))
      (node (ref "P8") (pin "12") (pinfunction "12_12") (pintype "passive"))
    )
    (net (code "51") (name "Net-(P-15-Pad7)") (class "Default")
      (node (ref "P-15") (pin "7") (pinfunction "7_7") (pintype "passive"))
      (node (ref "P8") (pin "14") (pinfunction "14_14") (pintype "passive"))
    )
    (net (code "52") (name "Net-(P9-Pad4)") (class "Default")
      (node (ref "P9") (pin "4") (pinfunction "4_4") (pintype "passive"))
      (node (ref "PGND") (pin "2") (pinfunction "2_2") (pintype "passive"))
    )
    (net (code "53") (name "Net-(P9-Pad6)") (class "Default")
      (node (ref "P9") (pin "6") (pinfunction "6_6") (pintype "passive"))
      (node (ref "PGND") (pin "3") (pinfunction "3_3") (pintype "passive"))
    )
    (net (code "54") (name "Net-(P9-Pad8)") (class "Default")
      (node (ref "P9") (pin "8") (pinfunction "8_8") (pintype "passive"))
      (node (ref "PGND") (pin "4") (pinfunction "4_4") (pintype "passive"))
    )
    (net (code "55") (name "Net-(P9-Pad10)") (class "Default")
      (node (ref "P9") (pin "10") (pinfunction "10_10") (pintype "passive"))
      (node (ref "PGND") (pin "5") (pinfunction "5_5") (pintype "passive"))
    )
    (net (code "56") (name "Net-(P9-Pad12)") (class "Default")
      (node (ref "P9") (pin "12") (pinfunction "12_12") (pintype "passive"))
      (node (ref "PGND") (pin "6") (pinfunction "6_6") (pintype "passive"))
    )
    (net (code "57") (name "Net-(P9-Pad14)") (class "Default")
      (node (ref "P9") (pin "14") (pinfunction "14_14") (pintype "passive"))
      (node (ref "PGND") (pin "7") (pinfunction "7_7") (pintype "passive"))
    )
    (net (code "58") (name "Net-(P15-Pad2)") (class "Default")
      (node (ref "P15") (pin "2") (pinfunction "2_2") (pintype "passive"))
      (node (ref "P7") (pin "4") (pinfunction "4_4") (pintype "passive"))
    )
    (net (code "59") (name "Net-(P15-Pad3)") (class "Default")
      (node (ref "P15") (pin "3") (pinfunction "3_3") (pintype "passive"))
      (node (ref "P7") (pin "6") (pinfunction "6_6") (pintype "passive"))
    )
    (net (code "60") (name "Net-(P15-Pad4)") (class "Default")
      (node (ref "P15") (pin "4") (pinfunction "4_4") (pintype "passive"))
      (node (ref "P7") (pin "8") (pinfunction "8_8") (pintype "passive"))
    )
    (net (code "61") (name "Net-(P15-Pad5)") (class "Default")
      (node (ref "P15") (pin "5") (pinfunction "5_5") (pintype "passive"))
      (node (ref "P7") (pin "10") (pinfunction "10_10") (pintype "passive"))
    )
    (net (code "62") (name "Net-(P15-Pad6)") (class "Default")
      (node (ref "P15") (pin "6") (pinfunction "6_6") (pintype "passive"))
      (node (ref "P7") (pin "12") (pinfunction "12_12") (pintype "passive"))
    )
    (net (code "63") (name "Net-(P15-Pad7)") (class "Default")
      (node (ref "P15") (pin "7") (pinfunction "7_7") (pintype "passive"))
      (node (ref "P7") (pin "14") (pinfunction "14_14") (pintype "passive"))
    )
    (net (code "64") (name "Net-(R2-TAP)") (class "Default")
      (node (ref "R2") (pin "3") (pinfunction "TAP_3") (pintype "passive"))
      (node (ref "R3") (pin "1") (pinfunction "1_1") (pintype "passive"))
    )
    (net (code "65") (name "Net-(R11-TAP)") (class "Default")
      (node (ref "R11") (pin "3") (pinfunction "TAP_3") (pintype "passive"))
      (node (ref "R12") (pin "1") (pinfunction "1_1") (pintype "passive"))
    )
    (net (code "66") (name "Net-(R14-TOP)") (class "Default")
      (node (ref "R14") (pin "1") (pinfunction "TOP_1") (pintype "passive"))
      (node (ref "U3") (pin "6") (pinfunction "DENINPUT_6") (pintype "passive"))
    )
    (net (code "67") (name "Net-(R16-TAP)") (class "Default")
      (node (ref "R16") (pin "3") (pinfunction "TAP_3") (pintype "passive"))
      (node (ref "R17") (pin "1") (pinfunction "1_1") (pintype "passive"))
    )
    (net (code "68") (name "Net-(R19-TAP)") (class "Default")
      (node (ref "R19") (pin "3") (pinfunction "TAP_3") (pintype "passive"))
      (node (ref "R20") (pin "1") (pinfunction "1_1") (pintype "passive"))
    )
    (net (code "69") (name "Net-(R21-TOP)") (class "Default")
      (node (ref "R21") (pin "1") (pinfunction "TOP_1") (pintype "passive"))
      (node (ref "U4") (pin "6") (pinfunction "DENINPUT_6") (pintype "passive"))
    )
    (net (code "70") (name "Net-(R22-TOP)") (class "Default")
      (node (ref "R22") (pin "1") (pinfunction "TOP_1") (pintype "passive"))
      (node (ref "U5") (pin "6") (pinfunction "DENINPUT_6") (pintype "passive"))
    )
    (net (code "71") (name "Net-(R77-BOT)") (class "Default")
      (node (ref "R77") (pin "2") (pinfunction "BOT_2") (pintype "passive"))
      (node (ref "U2") (pin "6") (pinfunction "DENINPUT_6") (pintype "passive"))
    )
    (net (code "72") (name "Net-(RB4-BOT)") (class "Default")
      (node (ref "CMB1") (pin "1") (pinfunction "1_1") (pintype "passive"))
      (node (ref "LM1") (pin "6") (pintype "passive"))
      (node (ref "RB1") (pin "2") (pinfunction "2_2") (pintype "passive"))
      (node (ref "RB4") (pin "2") (pinfunction "BOT_2") (pintype "passive"))
      (node (ref "RB4") (pin "3") (pinfunction "TAP_3") (pintype "passive"))
    )
    (net (code "73") (name "Net-(RB7-BOT)") (class "Default")
      (node (ref "CMB2") (pin "1") (pinfunction "1_1") (pintype "passive"))
      (node (ref "LM2") (pin "6") (pintype "passive"))
      (node (ref "RB5") (pin "2") (pinfunction "2_2") (pintype "passive"))
      (node (ref "RB7") (pin "2") (pinfunction "BOT_2") (pintype "passive"))
      (node (ref "RB7") (pin "3") (pinfunction "TAP_3") (pintype "passive"))
    )
    (net (code "74") (name "Net-(RM1-TOP)") (class "Default")
      (node (ref "RM1") (pin "1") (pinfunction "TOP_1") (pintype "passive"))
      (node (ref "U1") (pin "1") (pinfunction "IN+_1") (pintype "passive"))
    )
    (net (code "75") (name "Net-(U2-CAV)") (class "Default")
      (node (ref "C1") (pin "2") (pinfunction "2_2") (pintype "passive"))
      (node (ref "U2") (pin "10") (pinfunction "CAV_10") (pintype "passive"))
    )
    (net (code "76") (name "Net-(U2-OUTPUT)") (class "Default")
      (node (ref "R3") (pin "2") (pinfunction "2_2") (pintype "passive"))
      (node (ref "U2") (pin "4") (pinfunction "OUTPUT_4") (pintype "passive"))
    )
    (net (code "77") (name "Net-(U2-VIN)") (class "Default")
      (node (ref "R1") (pin "1") (pinfunction "1_1") (pintype "passive"))
      (node (ref "U2") (pin "15") (pinfunction "VIN_15") (pintype "passive"))
    )
    (net (code "78") (name "Net-(U3-CAV)") (class "Default")
      (node (ref "C2") (pin "2") (pinfunction "2_2") (pintype "passive"))
      (node (ref "U3") (pin "10") (pinfunction "CAV_10") (pintype "passive"))
    )
    (net (code "79") (name "Net-(U3-OUTPUT)") (class "Default")
      (node (ref "R12") (pin "2") (pinfunction "2_2") (pintype "passive"))
      (node (ref "U3") (pin "4") (pinfunction "OUTPUT_4") (pintype "passive"))
    )
    (net (code "80") (name "Net-(U3-VIN)") (class "Default")
      (node (ref "R10") (pin "1") (pinfunction "1_1") (pintype "passive"))
      (node (ref "U3") (pin "15") (pinfunction "VIN_15") (pintype "passive"))
    )
    (net (code "81") (name "Net-(U4-CAV)") (class "Default")
      (node (ref "CA2") (pin "2") (pinfunction "2_2") (pintype "passive"))
      (node (ref "U4") (pin "10") (pinfunction "CAV_10") (pintype "passive"))
    )
    (net (code "82") (name "Net-(U4-OUTPUT)") (class "Default")
      (node (ref "R17") (pin "2") (pinfunction "2_2") (pintype "passive"))
      (node (ref "U4") (pin "4") (pinfunction "OUTPUT_4") (pintype "passive"))
    )
    (net (code "83") (name "Net-(U4-VIN)") (class "Default")
      (node (ref "R15") (pin "1") (pinfunction "1_1") (pintype "passive"))
      (node (ref "U4") (pin "15") (pinfunction "VIN_15") (pintype "passive"))
    )
    (net (code "84") (name "Net-(U5-CAV)") (class "Default")
      (node (ref "C8") (pin "2") (pinfunction "2_2") (pintype "passive"))
      (node (ref "U5") (pin "10") (pinfunction "CAV_10") (pintype "passive"))
    )
    (net (code "85") (name "Net-(U5-OUTPUT)") (class "Default")
      (node (ref "R20") (pin "2") (pinfunction "2_2") (pintype "passive"))
      (node (ref "U5") (pin "4") (pinfunction "OUTPUT_4") (pintype "passive"))
    )
    (net (code "86") (name "Net-(U5-VIN)") (class "Default")
      (node (ref "R18") (pin "1") (pinfunction "1_1") (pintype "passive"))
      (node (ref "U5") (pin "15") (pinfunction "VIN_15") (pintype "passive"))
    )
    (net (code "87") (name "VCC") (class "Default")
      (node (ref "JP14") (pin "2") (pinfunction "2_2") (pintype "passive"))
      (node (ref "UF1") (pin "2") (pinfunction "IN+_2") (pintype "passive"))
    )
    (net (code "88") (name "VS") (class "Default")
      (node (ref "P1") (pin "1") (pinfunction "1_1") (pintype "passive"))
      (node (ref "P1") (pin "2") (pinfunction "2_2") (pintype "passive"))
      (node (ref "RB3") (pin "1") (pinfunction "1_1") (pintype "passive"))
    )
    (net (code "89") (name "unconnected-(U2-BUFF_OUT-Pad16)") (class "Default")
      (node (ref "U2") (pin "16") (pinfunction "BUFF_OUT_16") (pintype "passive"))
    )
    (net (code "90") (name "unconnected-(U2-CS-Pad5)") (class "Default")
      (node (ref "U2") (pin "5") (pinfunction "CS_5") (pintype "passive"))
    )
    (net (code "91") (name "unconnected-(U2-DB_OUTPUT-Pad7)") (class "Default")
      (node (ref "U2") (pin "7") (pinfunction "DB_OUTPUT_7") (pintype "passive"))
    )
    (net (code "92") (name "unconnected-(U2-NC-Pad2)") (class "Default")
      (node (ref "U2") (pin "2") (pinfunction "NC_2") (pintype "passive"))
    )
    (net (code "93") (name "unconnected-(U2-NC-Pad8)") (class "Default")
      (node (ref "U2") (pin "8") (pinfunction "NC_8") (pintype "passive"))
    )
    (net (code "94") (name "unconnected-(U2-NC-Pad9)") (class "Default")
      (node (ref "U2") (pin "9") (pinfunction "NC_9") (pintype "passive"))
    )
    (net (code "95") (name "unconnected-(U2-NC-Pad14)") (class "Default")
      (node (ref "U2") (pin "14") (pinfunction "NC_14") (pintype "passive"))
    )
    (net (code "96") (name "unconnected-(U3-BUFF_OUT-Pad16)") (class "Default")
      (node (ref "U3") (pin "16") (pinfunction "BUFF_OUT_16") (pintype "passive"))
    )
    (net (code "97") (name "unconnected-(U3-CS-Pad5)") (class "Default")
      (node (ref "U3") (pin "5") (pinfunction "CS_5") (pintype "passive"))
    )
    (net (code "98") (name "unconnected-(U3-DB_OUTPUT-Pad7)") (class "Default")
      (node (ref "U3") (pin "7") (pinfunction "DB_OUTPUT_7") (pintype "passive"))
    )
    (net (code "99") (name "unconnected-(U3-NC-Pad2)") (class "Default")
      (node (ref "U3") (pin "2") (pinfunction "NC_2") (pintype "passive"))
    )
    (net (code "100") (name "unconnected-(U3-NC-Pad8)") (class "Default")
      (node (ref "U3") (pin "8") (pinfunction "NC_8") (pintype "passive"))
    )
    (net (code "101") (name "unconnected-(U3-NC-Pad9)") (class "Default")
      (node (ref "U3") (pin "9") (pinfunction "NC_9") (pintype "passive"))
    )
    (net (code "102") (name "unconnected-(U3-NC-Pad14)") (class "Default")
      (node (ref "U3") (pin "14") (pinfunction "NC_14") (pintype "passive"))
    )
    (net (code "103") (name "unconnected-(U4-BUFF_OUT-Pad16)") (class "Default")
      (node (ref "U4") (pin "16") (pinfunction "BUFF_OUT_16") (pintype "passive"))
    )
    (net (code "104") (name "unconnected-(U4-CS-Pad5)") (class "Default")
      (node (ref "U4") (pin "5") (pinfunction "CS_5") (pintype "passive"))
    )
    (net (code "105") (name "unconnected-(U4-DB_OUTPUT-Pad7)") (class "Default")
      (node (ref "U4") (pin "7") (pinfunction "DB_OUTPUT_7") (pintype "passive"))
    )
    (net (code "106") (name "unconnected-(U4-NC-Pad2)") (class "Default")
      (node (ref "U4") (pin "2") (pinfunction "NC_2") (pintype "passive"))
    )
    (net (code "107") (name "unconnected-(U4-NC-Pad8)") (class "Default")
      (node (ref "U4") (pin "8") (pinfunction "NC_8") (pintype "passive"))
    )
    (net (code "108") (name "unconnected-(U4-NC-Pad9)") (class "Default")
      (node (ref "U4") (pin "9") (pinfunction "NC_9") (pintype "passive"))
    )
    (net (code "109") (name "unconnected-(U4-NC-Pad14)") (class "Default")
      (node (ref "U4") (pin "14") (pinfunction "NC_14") (pintype "passive"))
    )
    (net (code "110") (name "unconnected-(U5-BUFF_OUT-Pad16)") (class "Default")
      (node (ref "U5") (pin "16") (pinfunction "BUFF_OUT_16") (pintype "passive"))
    )
    (net (code "111") (name "unconnected-(U5-CS-Pad5)") (class "Default")
      (node (ref "U5") (pin "5") (pinfunction "CS_5") (pintype "passive"))
    )
    (net (code "112") (name "unconnected-(U5-DB_OUTPUT-Pad7)") (class "Default")
      (node (ref "U5") (pin "7") (pinfunction "DB_OUTPUT_7") (pintype "passive"))
    )
    (net (code "113") (name "unconnected-(U5-NC-Pad2)") (class "Default")
      (node (ref "U5") (pin "2") (pinfunction "NC_2") (pintype "passive"))
    )
    (net (code "114") (name "unconnected-(U5-NC-Pad8)") (class "Default")
      (node (ref "U5") (pin "8") (pinfunction "NC_8") (pintype "passive"))
    )
    (net (code "115") (name "unconnected-(U5-NC-Pad9)") (class "Default")
      (node (ref "U5") (pin "9") (pinfunction "NC_9") (pintype "passive"))
    )
    (net (code "116") (name "unconnected-(U5-NC-Pad14)") (class "Default")
      (node (ref "U5") (pin "14") (pinfunction "NC_14") (pintype "passive"))
    )
  )
)
